# LDR-2.net
KiCad netlist of a schematic drawn in EAGLE
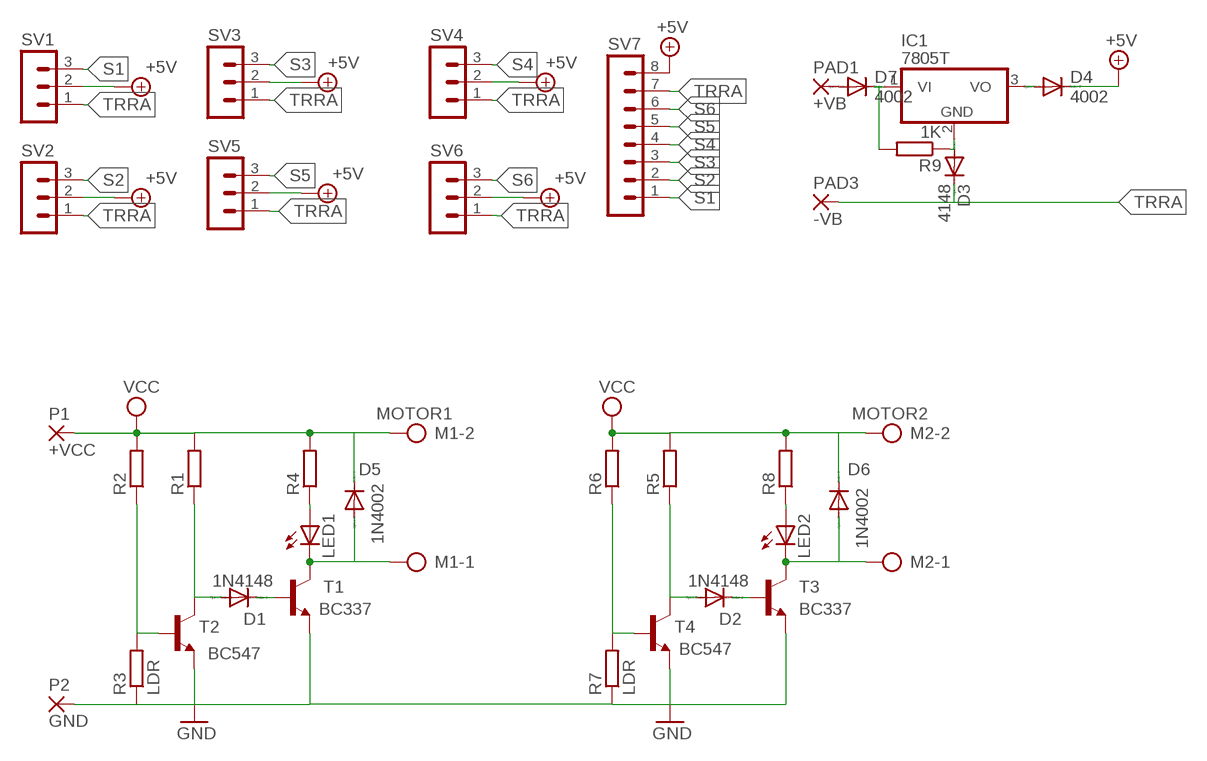
[diagram p0: schematic, sheet 1]

(export (version "E")
  (design (tool "Eeschema 10.0.6"))
  (components
    (comp (ref "D1")
      (value "1N4148")
      (footprint "eagle-import:DO35-7")
      (libsource (lib "eagle-import") (part "1N4148DO35-7"))
    )
    (comp (ref "D2")
      (value "1N4148")
      (footprint "eagle-import:DO35-7")
      (libsource (lib "eagle-import") (part "1N4148DO35-7"))
    )
    (comp (ref "D3")
      (value "4148")
      (footprint "eagle-import:DO35-7")
      (libsource (lib "eagle-import") (part "1N4148DO35-7"))
    )
    (comp (ref "D4")
      (value "4002")
      (footprint "eagle-import:DO35-7")
      (libsource (lib "eagle-import") (part "1N4148DO35-7"))
    )
    (comp (ref "D5")
      (value "1N4002")
      (footprint "eagle-import:DO41-10")
      (libsource (lib "eagle-import") (part "1N4933"))
    )
    (comp (ref "D6")
      (value "1N4002")
      (footprint "eagle-import:DO41-10")
      (libsource (lib "eagle-import") (part "1N4933"))
    )
    (comp (ref "D7")
      (value "4002")
      (footprint "eagle-import:DO35-7")
      (libsource (lib "eagle-import") (part "1N4148DO35-7"))
    )
    (comp (ref "IC1")
      (value "7805T")
      (footprint "eagle-import:TO220H")
      (libsource (lib "eagle-import") (part "78T05"))
    )
    (comp (ref "LED1")
      (value "LED3MM")
      (footprint "eagle-import:LED3MM")
      (libsource (lib "eagle-import") (part "LED3MM"))
    )
    (comp (ref "LED2")
      (value "LED3MM")
      (footprint "eagle-import:LED3MM")
      (libsource (lib "eagle-import") (part "LED3MM"))
    )
    (comp (ref "M1")
      (value "MOTOR1")
      (footprint "eagle-import:AK500_2")
      (libsource (lib "eagle-import") (part "AK500/2"))
    )
    (comp (ref "M2")
      (value "MOTOR2")
      (footprint "eagle-import:AK500_2")
      (libsource (lib "eagle-import") (part "AK500/2"))
    )
    (comp (ref "P1")
      (value "+VCC")
      (footprint "eagle-import:2,15_1,0")
      (libsource (lib "eagle-import") (part "WIREPAD2,15/1,0"))
    )
    (comp (ref "P2")
      (value "GND")
      (footprint "eagle-import:2,15_1,0")
      (libsource (lib "eagle-import") (part "WIREPAD2,15/1,0"))
    )
    (comp (ref "PAD1")
      (value "+VB")
      (footprint "eagle-import:1,6_0,9")
      (libsource (lib "eagle-import") (part "WIREPAD1,6/0,9"))
    )
    (comp (ref "PAD3")
      (value "-VB")
      (footprint "eagle-import:1,6_0,9")
      (libsource (lib "eagle-import") (part "WIREPAD1,6/0,9"))
    )
    (comp (ref "R1")
      (value "R-EU_0207/7")
      (footprint "eagle-import:0207_7")
      (libsource (lib "eagle-import") (part "R-EU_0207/7"))
    )
    (comp (ref "R2")
      (value "R-EU_0207/7")
      (footprint "eagle-import:0207_7")
      (libsource (lib "eagle-import") (part "R-EU_0207/7"))
    )
    (comp (ref "R3")
      (value "LDR")
      (footprint "eagle-import:0204_5")
      (libsource (lib "eagle-import") (part "R-EU_0204/5"))
    )
    (comp (ref "R4")
      (value "R-EU_0207/7")
      (footprint "eagle-import:0207_7")
      (libsource (lib "eagle-import") (part "R-EU_0207/7"))
    )
    (comp (ref "R5")
      (value "R-EU_0207/7")
      (footprint "eagle-import:0207_7")
      (libsource (lib "eagle-import") (part "R-EU_0207/7"))
    )
    (comp (ref "R6")
      (value "R-EU_0207/7")
      (footprint "eagle-import:0207_7")
      (libsource (lib "eagle-import") (part "R-EU_0207/7"))
    )
    (comp (ref "R7")
      (value "LDR")
      (footprint "eagle-import:0204_5")
      (libsource (lib "eagle-import") (part "R-EU_0204/5"))
    )
    (comp (ref "R8")
      (value "R-EU_0207/7")
      (footprint "eagle-import:0207_7")
      (libsource (lib "eagle-import") (part "R-EU_0207/7"))
    )
    (comp (ref "R9")
      (value "1K")
      (footprint "eagle-import:0207_7")
      (libsource (lib "eagle-import") (part "R-EU_0207/7"))
    )
    (comp (ref "SV1")
      (value "MA03-1")
      (footprint "eagle-import:MA03-1")
      (libsource (lib "eagle-import") (part "MA03-1"))
    )
    (comp (ref "SV2")
      (value "MA03-1")
      (footprint "eagle-import:MA03-1")
      (libsource (lib "eagle-import") (part "MA03-1"))
    )
    (comp (ref "SV3")
      (value "MA03-1")
      (footprint "eagle-import:MA03-1")
      (libsource (lib "eagle-import") (part "MA03-1"))
    )
    (comp (ref "SV4")
      (value "MA03-1")
      (footprint "eagle-import:MA03-1")
      (libsource (lib "eagle-import") (part "MA03-1"))
    )
    (comp (ref "SV5")
      (value "MA03-1")
      (footprint "eagle-import:MA03-1")
      (libsource (lib "eagle-import") (part "MA03-1"))
    )
    (comp (ref "SV6")
      (value "MA03-1")
      (footprint "eagle-import:MA03-1")
      (libsource (lib "eagle-import") (part "MA03-1"))
    )
    (comp (ref "SV7")
      (value "MA08-1")
      (footprint "eagle-import:MA08-1")
      (libsource (lib "eagle-import") (part "MA08-1"))
    )
    (comp (ref "T1")
      (value "BC337")
      (footprint "eagle-import:TO92-CBE")
      (libsource (lib "eagle-import") (part "-NPN-TO92-CBEBC337-25"))
    )
    (comp (ref "T2")
      (value "BC547")
      (footprint "eagle-import:TO92-CBE")
      (libsource (lib "eagle-import") (part "-NPN-TO92-CBEBC547"))
    )
    (comp (ref "T3")
      (value "BC337")
      (footprint "eagle-import:TO92-CBE")
      (libsource (lib "eagle-import") (part "-NPN-TO92-CBEBC337-25"))
    )
    (comp (ref "T4")
      (value "BC547")
      (footprint "eagle-import:TO92-CBE")
      (libsource (lib "eagle-import") (part "-NPN-TO92-CBEBC547"))
    )
  )
  (nets
    (net (code "1") (name "+5V") (class "Default")
      (node (ref "D4") (pin "C") (pinfunction "C_C") (pintype "passive"))
      (node (ref "SV1") (pin "2") (pinfunction "2_2") (pintype "passive"))
      (node (ref "SV2") (pin "2") (pinfunction "2_2") (pintype "passive"))
      (node (ref "SV3") (pin "2") (pinfunction "2_2") (pintype "passive"))
      (node (ref "SV4") (pin "2") (pinfunction "2_2") (pintype "passive"))
      (node (ref "SV5") (pin "2") (pinfunction "2_2") (pintype "passive"))
      (node (ref "SV6") (pin "2") (pinfunction "2_2") (pintype "passive"))
      (node (ref "SV7") (pin "8") (pinfunction "8_8") (pintype "passive"))
    )
    (net (code "2") (name "GND") (class "Default")
      (node (ref "P2") (pin "1") (pinfunction "P_1") (pintype "passive"))
      (node (ref "R3") (pin "1") (pinfunction "1_1") (pintype "passive"))
      (node (ref "R7") (pin "1") (pinfunction "1_1") (pintype "passive"))
      (node (ref "T1") (pin "E") (pinfunction "E_E") (pintype "passive"))
      (node (ref "T2") (pin "E") (pinfunction "E_E") (pintype "passive"))
      (node (ref "T3") (pin "E") (pinfunction "E_E") (pintype "passive"))
      (node (ref "T4") (pin "E") (pinfunction "E_E") (pintype "passive"))
    )
    (net (code "3") (name "Net-(D1-PadA)") (class "Default")
      (node (ref "D1") (pin "A") (pinfunction "A_A") (pintype "passive"))
      (node (ref "R1") (pin "1") (pinfunction "1_1") (pintype "passive"))
      (node (ref "T2") (pin "C") (pinfunction "C_C") (pintype "passive"))
    )
    (net (code "4") (name "Net-(D1-PadC)") (class "Default")
      (node (ref "D1") (pin "C") (pinfunction "C_C") (pintype "passive"))
      (node (ref "T1") (pin "B") (pinfunction "B_B") (pintype "passive"))
    )
    (net (code "5") (name "Net-(D2-PadA)") (class "Default")
      (node (ref "D2") (pin "A") (pinfunction "A_A") (pintype "passive"))
      (node (ref "R5") (pin "1") (pinfunction "1_1") (pintype "passive"))
      (node (ref "T4") (pin "C") (pinfunction "C_C") (pintype "passive"))
    )
    (net (code "6") (name "Net-(D2-PadC)") (class "Default")
      (node (ref "D2") (pin "C") (pinfunction "C_C") (pintype "passive"))
      (node (ref "T3") (pin "B") (pinfunction "B_B") (pintype "passive"))
    )
    (net (code "7") (name "Net-(IC1-GND)") (class "Default")
      (node (ref "D3") (pin "A") (pinfunction "A_A") (pintype "passive"))
      (node (ref "IC1") (pin "2") (pinfunction "GND_2") (pintype "passive"))
      (node (ref "R9") (pin "1") (pinfunction "1_1") (pintype "passive"))
    )
    (net (code "8") (name "Net-(IC1-VI)") (class "Default")
      (node (ref "D7") (pin "C") (pinfunction "C_C") (pintype "passive"))
      (node (ref "IC1") (pin "1") (pinfunction "VI_1") (pintype "input"))
      (node (ref "R9") (pin "2") (pinfunction "2_2") (pintype "passive"))
    )
    (net (code "9") (name "Net-(IC1-VO)") (class "Default")
      (node (ref "D4") (pin "A") (pinfunction "A_A") (pintype "passive"))
      (node (ref "IC1") (pin "3") (pinfunction "VO_3") (pintype "passive"))
    )
    (net (code "10") (name "Net-(LED1-C)") (class "Default")
      (node (ref "D5") (pin "A") (pinfunction "A_A") (pintype "passive"))
      (node (ref "LED1") (pin "K") (pinfunction "C_K") (pintype "passive"))
      (node (ref "M1") (pin "1") (pinfunction "KL_1") (pintype "passive"))
      (node (ref "T1") (pin "C") (pinfunction "C_C") (pintype "passive"))
    )
    (net (code "11") (name "Net-(LED1-PadA)") (class "Default")
      (node (ref "LED1") (pin "A") (pinfunction "A_A") (pintype "passive"))
      (node (ref "R4") (pin "1") (pinfunction "1_1") (pintype "passive"))
    )
    (net (code "12") (name "Net-(LED2-C)") (class "Default")
      (node (ref "D6") (pin "A") (pinfunction "A_A") (pintype "passive"))
      (node (ref "LED2") (pin "K") (pinfunction "C_K") (pintype "passive"))
      (node (ref "M2") (pin "1") (pinfunction "KL_1") (pintype "passive"))
      (node (ref "T3") (pin "C") (pinfunction "C_C") (pintype "passive"))
    )
    (net (code "13") (name "Net-(LED2-PadA)") (class "Default")
      (node (ref "LED2") (pin "A") (pinfunction "A_A") (pintype "passive"))
      (node (ref "R8") (pin "1") (pinfunction "1_1") (pintype "passive"))
    )
    (net (code "14") (name "Net-(PAD1-P)") (class "Default")
      (node (ref "D7") (pin "A") (pinfunction "A_A") (pintype "passive"))
      (node (ref "PAD1") (pin "1") (pinfunction "P_1") (pintype "passive"))
    )
    (net (code "15") (name "Net-(R2-Pad1)") (class "Default")
      (node (ref "R2") (pin "1") (pinfunction "1_1") (pintype "passive"))
      (node (ref "R3") (pin "2") (pinfunction "2_2") (pintype "passive"))
      (node (ref "T2") (pin "B") (pinfunction "B_B") (pintype "passive"))
    )
    (net (code "16") (name "Net-(R6-Pad1)") (class "Default")
      (node (ref "R6") (pin "1") (pinfunction "1_1") (pintype "passive"))
      (node (ref "R7") (pin "2") (pinfunction "2_2") (pintype "passive"))
      (node (ref "T4") (pin "B") (pinfunction "B_B") (pintype "passive"))
    )
    (net (code "17") (name "S1") (class "Default")
      (node (ref "SV1") (pin "3") (pinfunction "3_3") (pintype "passive"))
      (node (ref "SV7") (pin "1") (pinfunction "1_1") (pintype "passive"))
    )
    (net (code "18") (name "S2") (class "Default")
      (node (ref "SV2") (pin "3") (pinfunction "3_3") (pintype "passive"))
      (node (ref "SV7") (pin "2") (pinfunction "2_2") (pintype "passive"))
    )
    (net (code "19") (name "S3") (class "Default")
      (node (ref "SV3") (pin "3") (pinfunction "3_3") (pintype "passive"))
      (node (ref "SV7") (pin "3") (pinfunction "3_3") (pintype "passive"))
    )
    (net (code "20") (name "S4") (class "Default")
      (node (ref "SV4") (pin "3") (pinfunction "3_3") (pintype "passive"))
      (node (ref "SV7") (pin "4") (pinfunction "4_4") (pintype "passive"))
    )
    (net (code "21") (name "S5") (class "Default")
      (node (ref "SV5") (pin "3") (pinfunction "3_3") (pintype "passive"))
      (node (ref "SV7") (pin "5") (pinfunction "5_5") (pintype "passive"))
    )
    (net (code "22") (name "S6") (class "Default")
      (node (ref "SV6") (pin "3") (pinfunction "3_3") (pintype "passive"))
      (node (ref "SV7") (pin "6") (pinfunction "6_6") (pintype "passive"))
    )
    (net (code "23") (name "TRRA") (class "Default")
      (node (ref "D3") (pin "C") (pinfunction "C_C") (pintype "passive"))
      (node (ref "PAD3") (pin "1") (pinfunction "P_1") (pintype "passive"))
      (node (ref "SV1") (pin "1") (pinfunction "1_1") (pintype "passive"))
      (node (ref "SV2") (pin "1") (pinfunction "1_1") (pintype "passive"))
      (node (ref "SV3") (pin "1") (pinfunction "1_1") (pintype "passive"))
      (node (ref "SV4") (pin "1") (pinfunction "1_1") (pintype "passive"))
      (node (ref "SV5") (pin "1") (pinfunction "1_1") (pintype "passive"))
      (node (ref "SV6") (pin "1") (pinfunction "1_1") (pintype "passive"))
      (node (ref "SV7") (pin "7") (pinfunction "7_7") (pintype "passive"))
    )
    (net (code "24") (name "VCC") (class "Default")
      (node (ref "D5") (pin "C") (pinfunction "C_C") (pintype "passive"))
      (node (ref "D6") (pin "C") (pinfunction "C_C") (pintype "passive"))
      (node (ref "M1") (pin "2") (pinfunction "KL_2") (pintype "passive"))
      (node (ref "M2") (pin "2") (pinfunction "KL_2") (pintype "passive"))
      (node (ref "P1") (pin "1") (pinfunction "P_1") (pintype "passive"))
      (node (ref "R1") (pin "2") (pinfunction "2_2") (pintype "passive"))
      (node (ref "R2") (pin "2") (pinfunction "2_2") (pintype "passive"))
      (node (ref "R4") (pin "2") (pinfunction "2_2") (pintype "passive"))
      (node (ref "R5") (pin "2") (pinfunction "2_2") (pintype "passive"))
      (node (ref "R6") (pin "2") (pinfunction "2_2") (pintype "passive"))
      (node (ref "R8") (pin "2") (pinfunction "2_2") (pintype "passive"))
    )
  )
)
